# LB_BIT_w12_wirelessTransmitter_v03_2_2_O.net
KiCad netlist of a schematic drawn in EAGLE
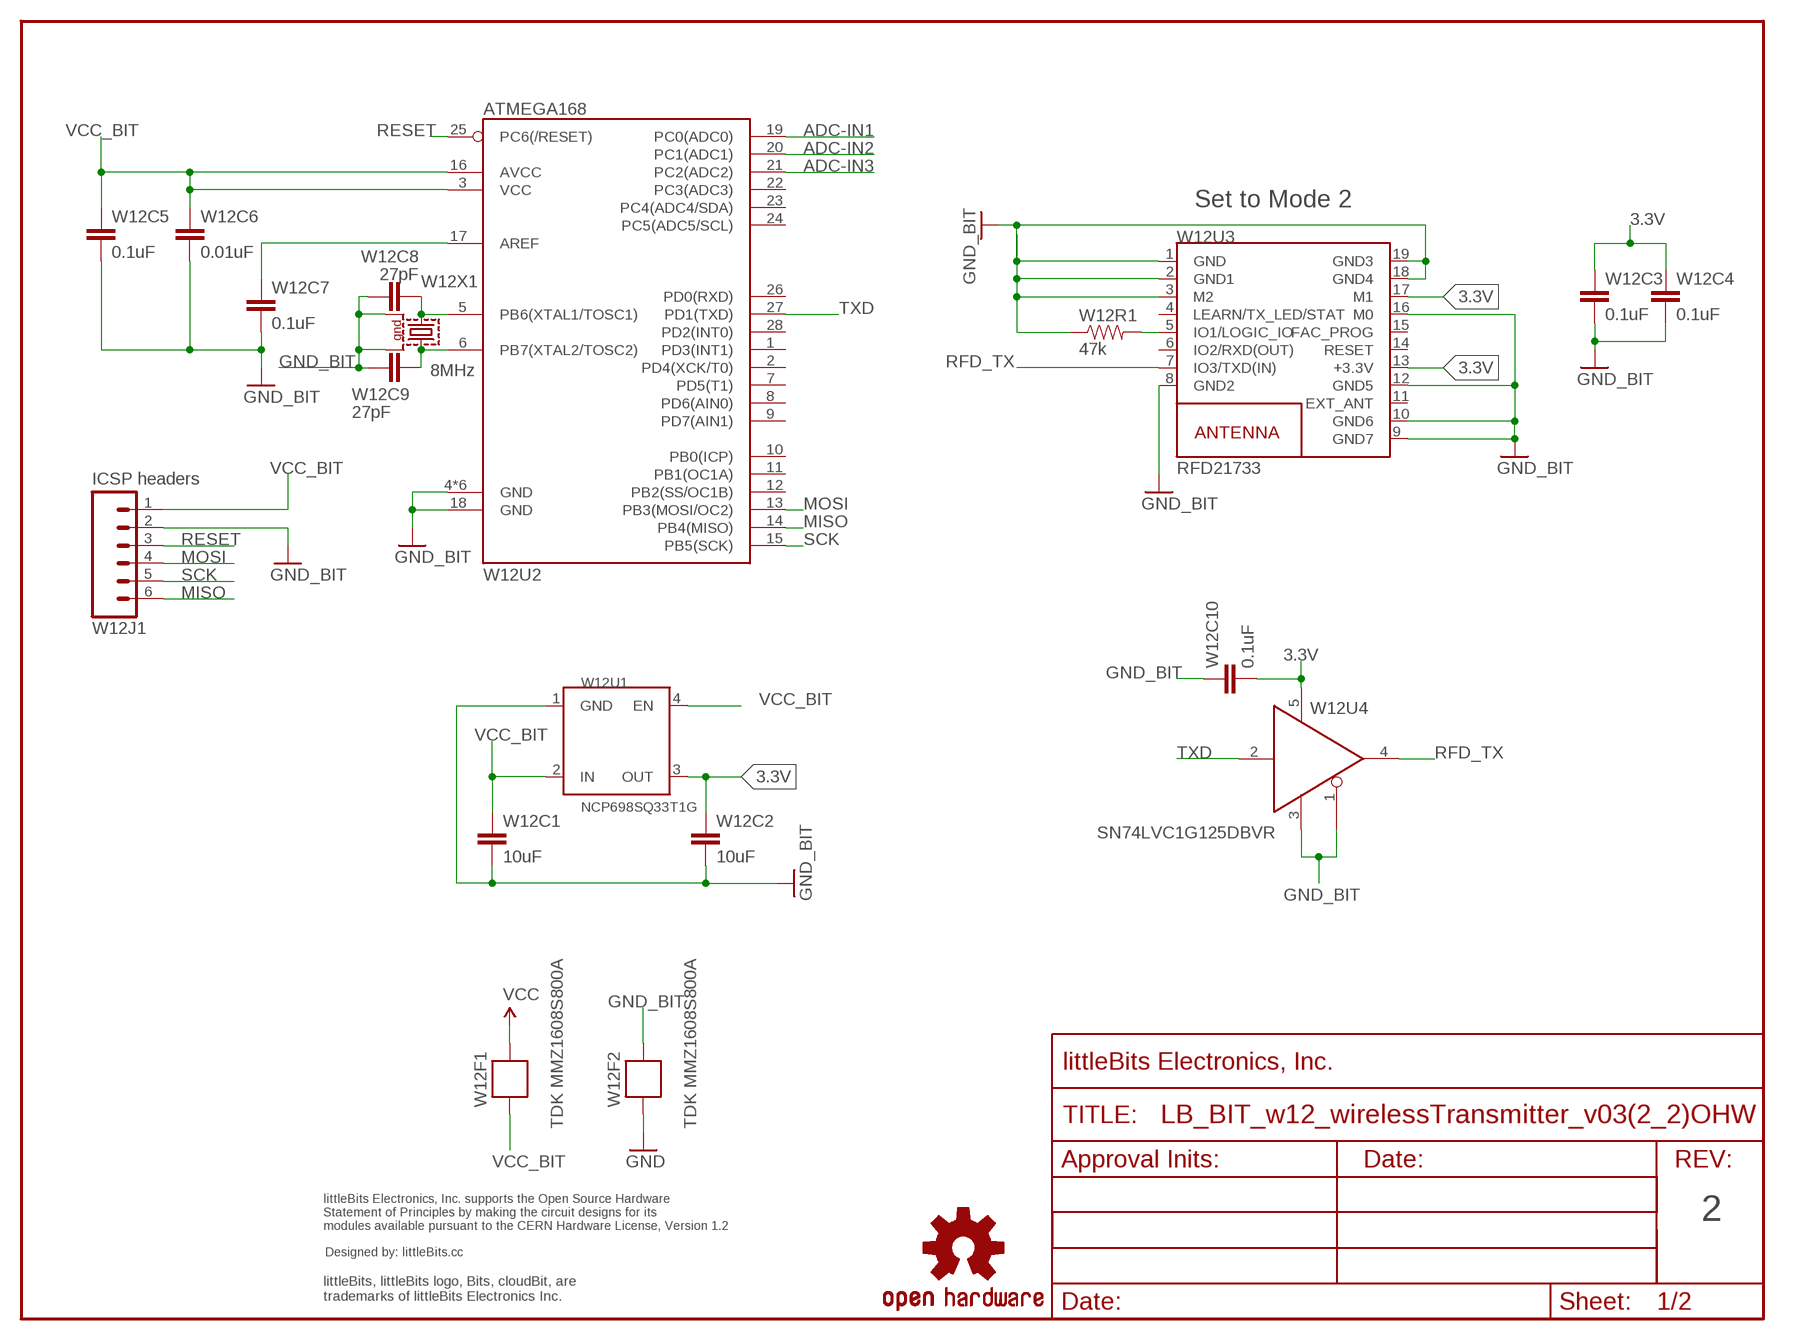
[diagram p0: schematic, sheet 1]
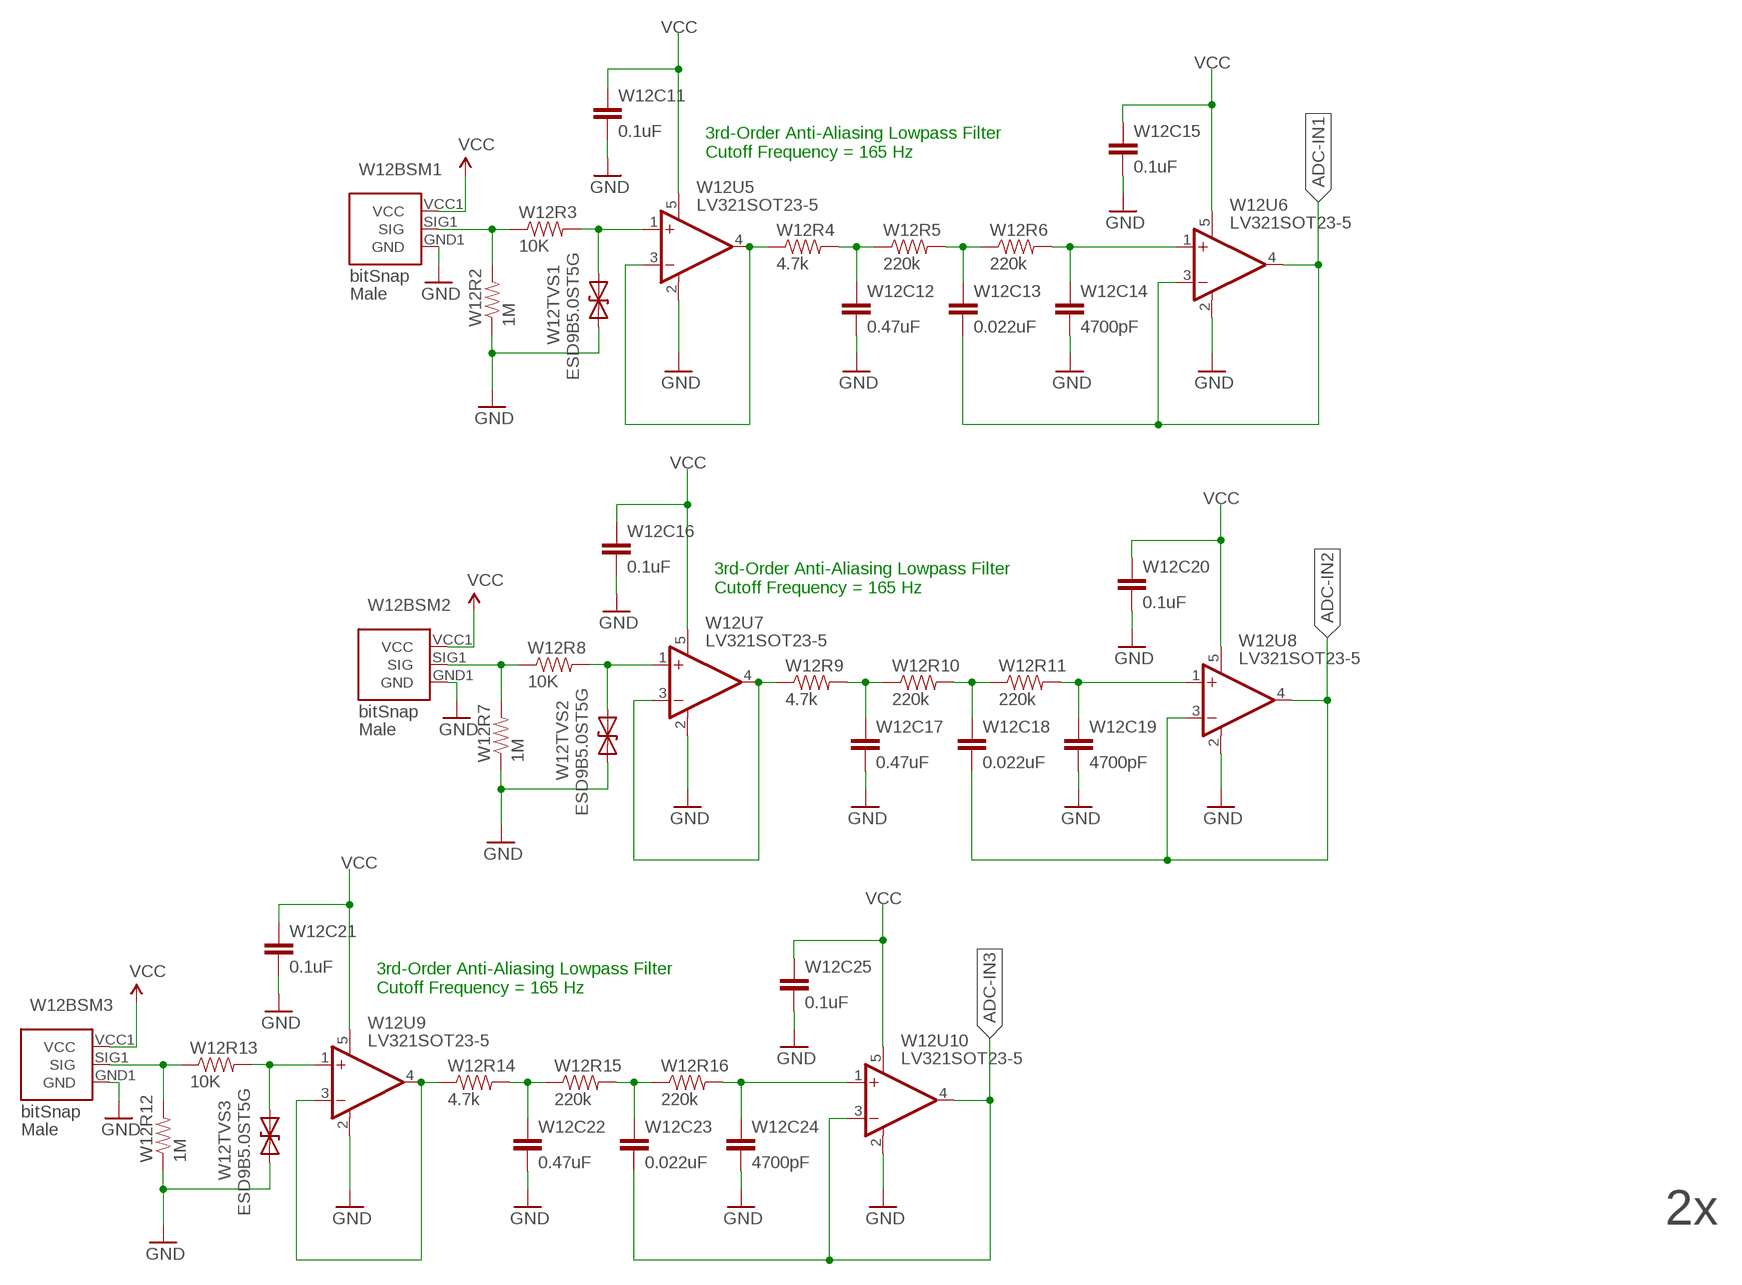
[diagram p1: schematic, sheet 2]

(export (version "E")
  (design (tool "Eeschema 10.0.6"))
  (components
    (comp (ref "W12BSM1")
      (value "BITSNAP_V03_MALE")
      (footprint "eagle-import:BITSNAP_V03_MALE")
      (libsource (lib "eagle-import") (part "BITSNAP_V03_MALE"))
    )
    (comp (ref "W12BSM2")
      (value "BITSNAP_V03_MALE")
      (footprint "eagle-import:BITSNAP_V03_MALE")
      (libsource (lib "eagle-import") (part "BITSNAP_V03_MALE"))
    )
    (comp (ref "W12BSM3")
      (value "BITSNAP_V03_MALE")
      (footprint "eagle-import:BITSNAP_V03_MALE")
      (libsource (lib "eagle-import") (part "BITSNAP_V03_MALE"))
    )
    (comp (ref "W12C11")
      (value "0.1uF")
      (footprint "eagle-import:0603-CAP")
      (libsource (lib "eagle-import") (part "CAP0603-CAP"))
    )
    (comp (ref "W12C12")
      (value "0.47uF")
      (footprint "eagle-import:CAP-0603")
      (libsource (lib "eagle-import") (part "CAPCAP-0603"))
    )
    (comp (ref "W12C13")
      (value "0.022uF")
      (footprint "eagle-import:CAP-0603")
      (libsource (lib "eagle-import") (part "CAPCAP-0603"))
    )
    (comp (ref "W12C14")
      (value "4700pF")
      (footprint "eagle-import:CAP-0603")
      (libsource (lib "eagle-import") (part "CAPCAP-0603"))
    )
    (comp (ref "W12C15")
      (value "0.1uF")
      (footprint "eagle-import:0603-CAP")
      (libsource (lib "eagle-import") (part "CAP0603-CAP"))
    )
    (comp (ref "W12C16")
      (value "0.1uF")
      (footprint "eagle-import:0603-CAP")
      (libsource (lib "eagle-import") (part "CAP0603-CAP"))
    )
    (comp (ref "W12C17")
      (value "0.47uF")
      (footprint "eagle-import:CAP-0603")
      (libsource (lib "eagle-import") (part "CAPCAP-0603"))
    )
    (comp (ref "W12C18")
      (value "0.022uF")
      (footprint "eagle-import:CAP-0603")
      (libsource (lib "eagle-import") (part "CAPCAP-0603"))
    )
    (comp (ref "W12C19")
      (value "4700pF")
      (footprint "eagle-import:CAP-0603")
      (libsource (lib "eagle-import") (part "CAPCAP-0603"))
    )
    (comp (ref "W12C20")
      (value "0.1uF")
      (footprint "eagle-import:0603-CAP")
      (libsource (lib "eagle-import") (part "CAP0603-CAP"))
    )
    (comp (ref "W12C21")
      (value "0.1uF")
      (footprint "eagle-import:0603-CAP")
      (libsource (lib "eagle-import") (part "CAP0603-CAP"))
    )
    (comp (ref "W12C22")
      (value "0.47uF")
      (footprint "eagle-import:CAP-0603")
      (libsource (lib "eagle-import") (part "CAPCAP-0603"))
    )
    (comp (ref "W12C23")
      (value "0.022uF")
      (footprint "eagle-import:CAP-0603")
      (libsource (lib "eagle-import") (part "CAPCAP-0603"))
    )
    (comp (ref "W12C24")
      (value "4700pF")
      (footprint "eagle-import:CAP-0603")
      (libsource (lib "eagle-import") (part "CAPCAP-0603"))
    )
    (comp (ref "W12C25")
      (value "0.1uF")
      (footprint "eagle-import:0603-CAP")
      (libsource (lib "eagle-import") (part "CAP0603-CAP"))
    )
    (comp (ref "W12R2")
      (value "1M")
      (footprint "eagle-import:0603-RES")
      (libsource (lib "eagle-import") (part "RESISTOR0603-RES"))
    )
    (comp (ref "W12R3")
      (value "10K")
      (footprint "eagle-import:0603-RES")
      (libsource (lib "eagle-import") (part "RESISTOR0603-RES"))
    )
    (comp (ref "W12R4")
      (value "4.7k")
      (footprint "eagle-import:RES-0603")
      (libsource (lib "eagle-import") (part "RESISTOR0603"))
    )
    (comp (ref "W12R5")
      (value "220k")
      (footprint "eagle-import:RES-0603")
      (libsource (lib "eagle-import") (part "RESISTOR0603"))
    )
    (comp (ref "W12R6")
      (value "220k")
      (footprint "eagle-import:RES-0603")
      (libsource (lib "eagle-import") (part "RESISTOR0603"))
    )
    (comp (ref "W12R7")
      (value "1M")
      (footprint "eagle-import:0603-RES")
      (libsource (lib "eagle-import") (part "RESISTOR0603-RES"))
    )
    (comp (ref "W12R8")
      (value "10K")
      (footprint "eagle-import:0603-RES")
      (libsource (lib "eagle-import") (part "RESISTOR0603-RES"))
    )
    (comp (ref "W12R9")
      (value "4.7k")
      (footprint "eagle-import:RES-0603")
      (libsource (lib "eagle-import") (part "RESISTOR0603"))
    )
    (comp (ref "W12R10")
      (value "220k")
      (footprint "eagle-import:RES-0603")
      (libsource (lib "eagle-import") (part "RESISTOR0603"))
    )
    (comp (ref "W12R11")
      (value "220k")
      (footprint "eagle-import:RES-0603")
      (libsource (lib "eagle-import") (part "RESISTOR0603"))
    )
    (comp (ref "W12R12")
      (value "1M")
      (footprint "eagle-import:0603-RES")
      (libsource (lib "eagle-import") (part "RESISTOR0603-RES"))
    )
    (comp (ref "W12R13")
      (value "10K")
      (footprint "eagle-import:0603-RES")
      (libsource (lib "eagle-import") (part "RESISTOR0603-RES"))
    )
    (comp (ref "W12R14")
      (value "4.7k")
      (footprint "eagle-import:RES-0603")
      (libsource (lib "eagle-import") (part "RESISTOR0603"))
    )
    (comp (ref "W12R15")
      (value "220k")
      (footprint "eagle-import:RES-0603")
      (libsource (lib "eagle-import") (part "RESISTOR0603"))
    )
    (comp (ref "W12R16")
      (value "220k")
      (footprint "eagle-import:RES-0603")
      (libsource (lib "eagle-import") (part "RESISTOR0603"))
    )
    (comp (ref "W12TVS1")
      (value "ESD9B5.0ST5G")
      (footprint "eagle-import:SOD-923")
      (libsource (lib "eagle-import") (part "DIODE-TVSSOD-923"))
    )
    (comp (ref "W12TVS2")
      (value "ESD9B5.0ST5G")
      (footprint "eagle-import:SOD-923")
      (libsource (lib "eagle-import") (part "DIODE-TVSSOD-923"))
    )
    (comp (ref "W12TVS3")
      (value "ESD9B5.0ST5G")
      (footprint "eagle-import:SOD-923")
      (libsource (lib "eagle-import") (part "DIODE-TVSSOD-923"))
    )
    (comp (ref "W12U5")
      (value "LV321SOT23-5")
      (footprint "eagle-import:SOT23-5")
      (libsource (lib "eagle-import") (part "LV321SOT23-5"))
    )
    (comp (ref "W12U6")
      (value "LV321SOT23-5")
      (footprint "eagle-import:SOT23-5")
      (libsource (lib "eagle-import") (part "LV321SOT23-5"))
    )
    (comp (ref "W12U7")
      (value "LV321SOT23-5")
      (footprint "eagle-import:SOT23-5")
      (libsource (lib "eagle-import") (part "LV321SOT23-5"))
    )
    (comp (ref "W12U8")
      (value "LV321SOT23-5")
      (footprint "eagle-import:SOT23-5")
      (libsource (lib "eagle-import") (part "LV321SOT23-5"))
    )
    (comp (ref "W12U9")
      (value "LV321SOT23-5")
      (footprint "eagle-import:SOT23-5")
      (libsource (lib "eagle-import") (part "LV321SOT23-5"))
    )
    (comp (ref "W12U10")
      (value "LV321SOT23-5")
      (footprint "eagle-import:SOT23-5")
      (libsource (lib "eagle-import") (part "LV321SOT23-5"))
    )
    (comp (ref "FRAME1")
      (value "FRAME-LETTER-OHWOHW")
      (footprint "eagle-import:FABDWG01-OHW")
      (libsource (lib "eagle-import") (part "FRAME-LETTER-OHWOHW"))
    )
    (comp (ref "U$15")
      (value "OSHWCREDIT")
      (footprint "eagle-import:OSHWCREDIT")
      (libsource (lib "eagle-import") (part "OSHWCREDIT"))
    )
    (comp (ref "U$31")
      (value "OSHW-LOGOL")
      (footprint "eagle-import:OSHW-LOGO-L")
      (libsource (lib "eagle-import") (part "OSHW-LOGOL"))
    )
    (comp (ref "W12C1")
      (value "10uF")
      (footprint "eagle-import:CAP-0603")
      (libsource (lib "eagle-import") (part "CAPCAP-0603"))
    )
    (comp (ref "W12C2")
      (value "10uF")
      (footprint "eagle-import:CAP-0603")
      (libsource (lib "eagle-import") (part "CAPCAP-0603"))
    )
    (comp (ref "W12C3")
      (value "0.1uF")
      (footprint "eagle-import:0603-CAP")
      (libsource (lib "eagle-import") (part "CAP0603-CAP"))
    )
    (comp (ref "W12C4")
      (value "0.1uF")
      (footprint "eagle-import:0603-CAP")
      (libsource (lib "eagle-import") (part "CAP0603-CAP"))
    )
    (comp (ref "W12C5")
      (value "0.1uF")
      (footprint "eagle-import:0603-CAP")
      (libsource (lib "eagle-import") (part "CAP0603-CAP"))
    )
    (comp (ref "W12C6")
      (value "0.01uF")
      (footprint "eagle-import:0603-CAP")
      (libsource (lib "eagle-import") (part "CAP0603-CAP"))
    )
    (comp (ref "W12C7")
      (value "0.1uF")
      (footprint "eagle-import:0603-CAP")
      (libsource (lib "eagle-import") (part "CAP0603-CAP"))
    )
    (comp (ref "W12C8")
      (value "27pF")
      (footprint "eagle-import:CAP-0603")
      (libsource (lib "eagle-import") (part "CAPCAP-0603"))
    )
    (comp (ref "W12C9")
      (value "27pF")
      (footprint "eagle-import:CAP-0603")
      (libsource (lib "eagle-import") (part "CAPCAP-0603"))
    )
    (comp (ref "W12C10")
      (value "0.1uF")
      (footprint "eagle-import:0603-CAP")
      (libsource (lib "eagle-import") (part "CAP0603-CAP"))
    )
    (comp (ref "W12F1")
      (value "TDK MMZ1608S800A")
      (footprint "eagle-import:R0603")
      (libsource (lib "eagle-import") (part "FERRITE-BEAD"))
    )
    (comp (ref "W12F2")
      (value "TDK MMZ1608S800A")
      (footprint "eagle-import:R0603")
      (libsource (lib "eagle-import") (part "FERRITE-BEAD"))
    )
    (comp (ref "W12J1")
      (value "ICSP headers")
      (footprint "eagle-import:SIP6-SM-0.1IN-NOS.S.")
      (libsource (lib "eagle-import") (part "HRD-60.1INCH_NO_SILKSCREEN"))
    )
    (comp (ref "W12R1")
      (value "47k")
      (footprint "eagle-import:0603-RES")
      (libsource (lib "eagle-import") (part "RESISTOR0603-RES"))
    )
    (comp (ref "W12U1")
      (value "NCP698SQ33T1G")
      (footprint "eagle-import:NCP698_SC82-AB")
      (libsource (lib "eagle-import") (part "NCP698"))
    )
    (comp (ref "W12U2")
      (value "ATMEGA168")
      (footprint "eagle-import:VQFN28")
      (libsource (lib "eagle-import") (part "ATMEGA168-28PINVFQFN-28"))
    )
    (comp (ref "W12U3")
      (value "RFD21733")
      (footprint "eagle-import:RFD21733")
      (libsource (lib "eagle-import") (part "RFD_CHIP"))
    )
    (comp (ref "W12U4")
      (value "SN74LVC1G125DBVR")
      (footprint "eagle-import:SOT23-5")
      (libsource (lib "eagle-import") (part "5V_TO_3.3V_LEVEL-SHIFTERSOT23-5"))
    )
    (comp (ref "W12X1")
      (value "8MHz")
      (footprint "eagle-import:CRYSTAL-SMD-7B-SERIES-5X3.2MM")
      (fields (field (name "MFG") "TXC") (field (name "MPN") "7B SERIES"))
      (libsource (lib "eagle-import") (part "CRYSTAL-SMD-7B-SERIES-TXC"))
    )
  )
  (nets
    (net (code "1") (name "3.3V") (class "Default")
      (node (ref "W12C10") (pin "2") (pinfunction "2_2") (pintype "passive"))
      (node (ref "W12C2") (pin "1") (pinfunction "1_1") (pintype "passive"))
      (node (ref "W12C3") (pin "1") (pinfunction "1_1") (pintype "passive"))
      (node (ref "W12C4") (pin "1") (pinfunction "1_1") (pintype "passive"))
      (node (ref "W12U1") (pin "3") (pinfunction "OUT_3") (pintype "bidirectional"))
      (node (ref "W12U3") (pin "13") (pinfunction "+3.3V_13") (pintype "bidirectional"))
      (node (ref "W12U3") (pin "17") (pinfunction "M1_17") (pintype "bidirectional"))
      (node (ref "W12U4") (pin "5") (pinfunction "5_5") (pintype "bidirectional"))
    )
    (net (code "2") (name "ADC-IN1") (class "Default")
      (node (ref "W12C13") (pin "2") (pinfunction "2_2") (pintype "passive"))
      (node (ref "W12U2") (pin "19") (pinfunction "PC0(ADC0)_19") (pintype "bidirectional"))
      (node (ref "W12U6") (pin "3") (pinfunction "-IN_3") (pintype "input"))
      (node (ref "W12U6") (pin "4") (pinfunction "OUT_4") (pintype "output"))
    )
    (net (code "3") (name "ADC-IN2") (class "Default")
      (node (ref "W12C18") (pin "2") (pinfunction "2_2") (pintype "passive"))
      (node (ref "W12U2") (pin "20") (pinfunction "PC1(ADC1)_20") (pintype "bidirectional"))
      (node (ref "W12U8") (pin "3") (pinfunction "-IN_3") (pintype "input"))
      (node (ref "W12U8") (pin "4") (pinfunction "OUT_4") (pintype "output"))
    )
    (net (code "4") (name "ADC-IN3") (class "Default")
      (node (ref "W12C23") (pin "2") (pinfunction "2_2") (pintype "passive"))
      (node (ref "W12U10") (pin "3") (pinfunction "-IN_3") (pintype "input"))
      (node (ref "W12U10") (pin "4") (pinfunction "OUT_4") (pintype "output"))
      (node (ref "W12U2") (pin "21") (pinfunction "PC2(ADC2)_21") (pintype "bidirectional"))
    )
    (net (code "5") (name "GND") (class "Default")
      (node (ref "W12BSM1") (pin "GND1") (pinfunction "GND_GND1") (pintype "bidirectional"))
      (node (ref "W12BSM2") (pin "GND1") (pinfunction "GND_GND1") (pintype "bidirectional"))
      (node (ref "W12BSM3") (pin "GND1") (pinfunction "GND_GND1") (pintype "bidirectional"))
      (node (ref "W12C11") (pin "2") (pinfunction "2_2") (pintype "passive"))
      (node (ref "W12C12") (pin "2") (pinfunction "2_2") (pintype "passive"))
      (node (ref "W12C14") (pin "2") (pinfunction "2_2") (pintype "passive"))
      (node (ref "W12C15") (pin "2") (pinfunction "2_2") (pintype "passive"))
      (node (ref "W12C16") (pin "2") (pinfunction "2_2") (pintype "passive"))
      (node (ref "W12C17") (pin "2") (pinfunction "2_2") (pintype "passive"))
      (node (ref "W12C19") (pin "2") (pinfunction "2_2") (pintype "passive"))
      (node (ref "W12C20") (pin "2") (pinfunction "2_2") (pintype "passive"))
      (node (ref "W12C21") (pin "2") (pinfunction "2_2") (pintype "passive"))
      (node (ref "W12C22") (pin "2") (pinfunction "2_2") (pintype "passive"))
      (node (ref "W12C24") (pin "2") (pinfunction "2_2") (pintype "passive"))
      (node (ref "W12C25") (pin "2") (pinfunction "2_2") (pintype "passive"))
      (node (ref "W12F2") (pin "2") (pinfunction "P$2_2") (pintype "bidirectional"))
      (node (ref "W12R12") (pin "1") (pinfunction "1_1") (pintype "passive"))
      (node (ref "W12R2") (pin "1") (pinfunction "1_1") (pintype "passive"))
      (node (ref "W12R7") (pin "1") (pinfunction "1_1") (pintype "passive"))
      (node (ref "W12TVS1") (pin "1") (pinfunction "A_1") (pintype "passive"))
      (node (ref "W12TVS2") (pin "1") (pinfunction "A_1") (pintype "passive"))
      (node (ref "W12TVS3") (pin "1") (pinfunction "A_1") (pintype "passive"))
      (node (ref "W12U10") (pin "2") (pinfunction "V-_2") (pintype "power_in"))
      (node (ref "W12U5") (pin "2") (pinfunction "V-_2") (pintype "power_in"))
      (node (ref "W12U6") (pin "2") (pinfunction "V-_2") (pintype "power_in"))
      (node (ref "W12U7") (pin "2") (pinfunction "V-_2") (pintype "power_in"))
      (node (ref "W12U8") (pin "2") (pinfunction "V-_2") (pintype "power_in"))
      (node (ref "W12U9") (pin "2") (pinfunction "V-_2") (pintype "power_in"))
    )
    (net (code "6") (name "GND_BIT") (class "Default")
      (node (ref "W12C1") (pin "2") (pinfunction "2_2") (pintype "passive"))
      (node (ref "W12C10") (pin "1") (pinfunction "1_1") (pintype "passive"))
      (node (ref "W12C2") (pin "2") (pinfunction "2_2") (pintype "passive"))
      (node (ref "W12C3") (pin "2") (pinfunction "2_2") (pintype "passive"))
      (node (ref "W12C4") (pin "2") (pinfunction "2_2") (pintype "passive"))
      (node (ref "W12C5") (pin "2") (pinfunction "2_2") (pintype "passive"))
      (node (ref "W12C6") (pin "2") (pinfunction "2_2") (pintype "passive"))
      (node (ref "W12C7") (pin "2") (pinfunction "2_2") (pintype "passive"))
      (node (ref "W12C8") (pin "1") (pinfunction "1_1") (pintype "passive"))
      (node (ref "W12C9") (pin "2") (pinfunction "2_2") (pintype "passive"))
      (node (ref "W12F2") (pin "1") (pinfunction "P$1_1") (pintype "bidirectional"))
      (node (ref "W12J1") (pin "2") (pinfunction "2_2") (pintype "passive"))
      (node (ref "W12R1") (pin "1") (pinfunction "1_1") (pintype "passive"))
      (node (ref "W12U1") (pin "1") (pinfunction "GND_1") (pintype "bidirectional"))
      (node (ref "W12U2") (pin "18") (pinfunction "GND_18") (pintype "bidirectional"))
      (node (ref "W12U2") (pin "4") (pinfunction "GND_4") (pintype "bidirectional"))
      (node (ref "W12U2") (pin "TH") (pinfunction "GND_TH") (pintype "bidirectional"))
      (node (ref "W12U2") (pin "TH@1") (pinfunction "GND_TH@1") (pintype "bidirectional"))
      (node (ref "W12U2") (pin "TH@2") (pinfunction "GND_TH@2") (pintype "bidirectional"))
      (node (ref "W12U2") (pin "TH@3") (pinfunction "GND_TH@3") (pintype "bidirectional"))
      (node (ref "W12U2") (pin "TH@4") (pinfunction "GND_TH@4") (pintype "bidirectional"))
      (node (ref "W12U3") (pin "1") (pinfunction "GND_1") (pintype "bidirectional"))
      (node (ref "W12U3") (pin "10") (pinfunction "GND6_10") (pintype "bidirectional"))
      (node (ref "W12U3") (pin "12") (pinfunction "GND5_12") (pintype "bidirectional"))
      (node (ref "W12U3") (pin "16") (pinfunction "M0_16") (pintype "bidirectional"))
      (node (ref "W12U3") (pin "18") (pinfunction "GND4_18") (pintype "bidirectional"))
      (node (ref "W12U3") (pin "19") (pinfunction "GND3_19") (pintype "bidirectional"))
      (node (ref "W12U3") (pin "2") (pinfunction "GND1_2") (pintype "bidirectional"))
      (node (ref "W12U3") (pin "3") (pinfunction "M2_3") (pintype "bidirectional"))
      (node (ref "W12U3") (pin "8") (pinfunction "GND2_8") (pintype "bidirectional"))
      (node (ref "W12U3") (pin "9") (pinfunction "GND7_9") (pintype "bidirectional"))
      (node (ref "W12U4") (pin "1") (pinfunction "1_1") (pintype "bidirectional"))
      (node (ref "W12U4") (pin "3") (pinfunction "3_3") (pintype "bidirectional"))
      (node (ref "W12X1") (pin "P$2") (pinfunction "2_P$2") (pintype "passive"))
      (node (ref "W12X1") (pin "P$4") (pinfunction "4_P$4") (pintype "passive"))
    )
    (net (code "7") (name "MISO") (class "Default")
      (node (ref "W12J1") (pin "6") (pinfunction "6_6") (pintype "passive"))
      (node (ref "W12U2") (pin "14") (pinfunction "PB4(MISO)_14") (pintype "bidirectional"))
    )
    (net (code "8") (name "MOSI") (class "Default")
      (node (ref "W12J1") (pin "4") (pinfunction "4_4") (pintype "passive"))
      (node (ref "W12U2") (pin "13") (pinfunction "PB3(MOSI/OC2)_13") (pintype "bidirectional"))
    )
    (net (code "9") (name "Net-(W12BSM1-SIG)") (class "Default")
      (node (ref "W12BSM1") (pin "SIG1") (pinfunction "SIG_SIG1") (pintype "bidirectional"))
      (node (ref "W12R2") (pin "2") (pinfunction "2_2") (pintype "passive"))
      (node (ref "W12R3") (pin "1") (pinfunction "1_1") (pintype "passive"))
    )
    (net (code "10") (name "Net-(W12BSM2-SIG)") (class "Default")
      (node (ref "W12BSM2") (pin "SIG1") (pinfunction "SIG_SIG1") (pintype "bidirectional"))
      (node (ref "W12R7") (pin "2") (pinfunction "2_2") (pintype "passive"))
      (node (ref "W12R8") (pin "1") (pinfunction "1_1") (pintype "passive"))
    )
    (net (code "11") (name "Net-(W12BSM3-SIG)") (class "Default")
      (node (ref "W12BSM3") (pin "SIG1") (pinfunction "SIG_SIG1") (pintype "bidirectional"))
      (node (ref "W12R12") (pin "2") (pinfunction "2_2") (pintype "passive"))
      (node (ref "W12R13") (pin "1") (pinfunction "1_1") (pintype "passive"))
    )
    (net (code "12") (name "Net-(W12C12-Pad1)") (class "Default")
      (node (ref "W12C12") (pin "1") (pinfunction "1_1") (pintype "passive"))
      (node (ref "W12R4") (pin "2") (pinfunction "2_2") (pintype "passive"))
      (node (ref "W12R5") (pin "1") (pinfunction "1_1") (pintype "passive"))
    )
    (net (code "13") (name "Net-(W12C13-Pad1)") (class "Default")
      (node (ref "W12C13") (pin "1") (pinfunction "1_1") (pintype "passive"))
      (node (ref "W12R5") (pin "2") (pinfunction "2_2") (pintype "passive"))
      (node (ref "W12R6") (pin "1") (pinfunction "1_1") (pintype "passive"))
    )
    (net (code "14") (name "Net-(W12C17-Pad1)") (class "Default")
      (node (ref "W12C17") (pin "1") (pinfunction "1_1") (pintype "passive"))
      (node (ref "W12R10") (pin "1") (pinfunction "1_1") (pintype "passive"))
      (node (ref "W12R9") (pin "2") (pinfunction "2_2") (pintype "passive"))
    )
    (net (code "15") (name "Net-(W12C18-Pad1)") (class "Default")
      (node (ref "W12C18") (pin "1") (pinfunction "1_1") (pintype "passive"))
      (node (ref "W12R10") (pin "2") (pinfunction "2_2") (pintype "passive"))
      (node (ref "W12R11") (pin "1") (pinfunction "1_1") (pintype "passive"))
    )
    (net (code "16") (name "Net-(W12C22-Pad1)") (class "Default")
      (node (ref "W12C22") (pin "1") (pinfunction "1_1") (pintype "passive"))
      (node (ref "W12R14") (pin "2") (pinfunction "2_2") (pintype "passive"))
      (node (ref "W12R15") (pin "1") (pinfunction "1_1") (pintype "passive"))
    )
    (net (code "17") (name "Net-(W12C23-Pad1)") (class "Default")
      (node (ref "W12C23") (pin "1") (pinfunction "1_1") (pintype "passive"))
      (node (ref "W12R15") (pin "2") (pinfunction "2_2") (pintype "passive"))
      (node (ref "W12R16") (pin "1") (pinfunction "1_1") (pintype "passive"))
    )
    (net (code "18") (name "Net-(W12TVS1-C)") (class "Default")
      (node (ref "W12R3") (pin "2") (pinfunction "2_2") (pintype "passive"))
      (node (ref "W12TVS1") (pin "2") (pinfunction "C_2") (pintype "passive"))
      (node (ref "W12U5") (pin "1") (pinfunction "+IN_1") (pintype "input"))
    )
    (net (code "19") (name "Net-(W12TVS2-C)") (class "Default")
      (node (ref "W12R8") (pin "2") (pinfunction "2_2") (pintype "passive"))
      (node (ref "W12TVS2") (pin "2") (pinfunction "C_2") (pintype "passive"))
      (node (ref "W12U7") (pin "1") (pinfunction "+IN_1") (pintype "input"))
    )
    (net (code "20") (name "Net-(W12TVS3-C)") (class "Default")
      (node (ref "W12R13") (pin "2") (pinfunction "2_2") (pintype "passive"))
      (node (ref "W12TVS3") (pin "2") (pinfunction "C_2") (pintype "passive"))
      (node (ref "W12U9") (pin "1") (pinfunction "+IN_1") (pintype "input"))
    )
    (net (code "21") (name "Net-(W12U2-AREF)") (class "Default")
      (node (ref "W12C7") (pin "1") (pinfunction "1_1") (pintype "passive"))
      (node (ref "W12U2") (pin "17") (pinfunction "AREF_17") (pintype "bidirectional"))
    )
    (net (code "22") (name "Net-(W12U2-PB6(XTAL1{slash}TOSC1))") (class "Default")
      (node (ref "W12C8") (pin "2") (pinfunction "2_2") (pintype "passive"))
      (node (ref "W12U2") (pin "5") (pinfunction "PB6(XTAL1/TOSC1)_5") (pintype "bidirectional"))
      (node (ref "W12X1") (pin "P$1") (pinfunction "1_P$1") (pintype "passive"))
    )
    (net (code "23") (name "Net-(W12U2-PB7(XTAL2{slash}TOSC2))") (class "Default")
      (node (ref "W12C9") (pin "1") (pinfunction "1_1") (pintype "passive"))
      (node (ref "W12U2") (pin "6") (pinfunction "PB7(XTAL2/TOSC2)_6") (pintype "bidirectional"))
      (node (ref "W12X1") (pin "P$3") (pinfunction "3_P$3") (pintype "passive"))
    )
    (net (code "24") (name "Net-(W12U3-IO1{slash}LOGIC_IO)") (class "Default")
      (node (ref "W12R1") (pin "2") (pinfunction "2_2") (pintype "passive"))
      (node (ref "W12U3") (pin "5") (pinfunction "IO1/LOGIC_IO_5") (pintype "bidirectional"))
    )
    (net (code "25") (name "Net-(W12U5--IN)") (class "Default")
      (node (ref "W12R4") (pin "1") (pinfunction "1_1") (pintype "passive"))
      (node (ref "W12U5") (pin "3") (pinfunction "-IN_3") (pintype "input"))
      (node (ref "W12U5") (pin "4") (pinfunction "OUT_4") (pintype "output"))
    )
    (net (code "26") (name "Net-(W12U6-+IN)") (class "Default")
      (node (ref "W12C14") (pin "1") (pinfunction "1_1") (pintype "passive"))
      (node (ref "W12R6") (pin "2") (pinfunction "2_2") (pintype "passive"))
      (node (ref "W12U6") (pin "1") (pinfunction "+IN_1") (pintype "input"))
    )
    (net (code "27") (name "Net-(W12U7--IN)") (class "Default")
      (node (ref "W12R9") (pin "1") (pinfunction "1_1") (pintype "passive"))
      (node (ref "W12U7") (pin "3") (pinfunction "-IN_3") (pintype "input"))
      (node (ref "W12U7") (pin "4") (pinfunction "OUT_4") (pintype "output"))
    )
    (net (code "28") (name "Net-(W12U8-+IN)") (class "Default")
      (node (ref "W12C19") (pin "1") (pinfunction "1_1") (pintype "passive"))
      (node (ref "W12R11") (pin "2") (pinfunction "2_2") (pintype "passive"))
      (node (ref "W12U8") (pin "1") (pinfunction "+IN_1") (pintype "input"))
    )
    (net (code "29") (name "Net-(W12U9--IN)") (class "Default")
      (node (ref "W12R14") (pin "1") (pinfunction "1_1") (pintype "passive"))
      (node (ref "W12U9") (pin "3") (pinfunction "-IN_3") (pintype "input"))
      (node (ref "W12U9") (pin "4") (pinfunction "OUT_4") (pintype "output"))
    )
    (net (code "30") (name "Net-(W12U10-+IN)") (class "Default")
      (node (ref "W12C24") (pin "1") (pinfunction "1_1") (pintype "passive"))
      (node (ref "W12R16") (pin "2") (pinfunction "2_2") (pintype "passive"))
      (node (ref "W12U10") (pin "1") (pinfunction "+IN_1") (pintype "input"))
    )
    (net (code "31") (name "RESET") (class "Default")
      (node (ref "W12J1") (pin "3") (pinfunction "3_3") (pintype "passive"))
      (node (ref "W12U2") (pin "25") (pinfunction "PC6(/RESET)_25") (pintype "bidirectional"))
    )
    (net (code "32") (name "RFD_TX") (class "Default")
      (node (ref "W12U3") (pin "7") (pinfunction "IO3/TXD(IN)_7") (pintype "bidirectional"))
      (node (ref "W12U4") (pin "4") (pinfunction "4_4") (pintype "bidirectional"))
    )
    (net (code "33") (name "SCK") (class "Default")
      (node (ref "W12J1") (pin "5") (pinfunction "5_5") (pintype "passive"))
      (node (ref "W12U2") (pin "15") (pinfunction "PB5(SCK)_15") (pintype "bidirectional"))
    )
    (net (code "34") (name "TXD") (class "Default")
      (node (ref "W12U2") (pin "27") (pinfunction "PD1(TXD)_27") (pintype "bidirectional"))
      (node (ref "W12U4") (pin "2") (pinfunction "2_2") (pintype "bidirectional"))
    )
    (net (code "35") (name "VCC") (class "Default")
      (node (ref "W12BSM1") (pin "VCC1") (pinfunction "VCC_VCC1") (pintype "bidirectional"))
      (node (ref "W12BSM2") (pin "VCC1") (pinfunction "VCC_VCC1") (pintype "bidirectional"))
      (node (ref "W12BSM3") (pin "VCC1") (pinfunction "VCC_VCC1") (pintype "bidirectional"))
      (node (ref "W12C11") (pin "1") (pinfunction "1_1") (pintype "passive"))
      (node (ref "W12C15") (pin "1") (pinfunction "1_1") (pintype "passive"))
      (node (ref "W12C16") (pin "1") (pinfunction "1_1") (pintype "passive"))
      (node (ref "W12C20") (pin "1") (pinfunction "1_1") (pintype "passive"))
      (node (ref "W12C21") (pin "1") (pinfunction "1_1") (pintype "passive"))
      (node (ref "W12C25") (pin "1") (pinfunction "1_1") (pintype "passive"))
      (node (ref "W12F1") (pin "1") (pinfunction "P$1_1") (pintype "bidirectional"))
      (node (ref "W12U10") (pin "5") (pinfunction "V+_5") (pintype "power_in"))
      (node (ref "W12U5") (pin "5") (pinfunction "V+_5") (pintype "power_in"))
      (node (ref "W12U6") (pin "5") (pinfunction "V+_5") (pintype "power_in"))
      (node (ref "W12U7") (pin "5") (pinfunction "V+_5") (pintype "power_in"))
      (node (ref "W12U8") (pin "5") (pinfunction "V+_5") (pintype "power_in"))
      (node (ref "W12U9") (pin "5") (pinfunction "V+_5") (pintype "power_in"))
    )
    (net (code "36") (name "VCC_BIT") (class "Default")
      (node (ref "W12C1") (pin "1") (pinfunction "1_1") (pintype "passive"))
      (node (ref "W12C5") (pin "1") (pinfunction "1_1") (pintype "passive"))
      (node (ref "W12C6") (pin "1") (pinfunction "1_1") (pintype "passive"))
      (node (ref "W12F1") (pin "2") (pinfunction "P$2_2") (pintype "bidirectional"))
      (node (ref "W12J1") (pin "1") (pinfunction "1_1") (pintype "passive"))
      (node (ref "W12U1") (pin "2") (pinfunction "IN_2") (pintype "bidirectional"))
      (node (ref "W12U1") (pin "4") (pinfunction "EN_4") (pintype "bidirectional"))
      (node (ref "W12U2") (pin "16") (pinfunction "AVCC_16") (pintype "bidirectional"))
      (node (ref "W12U2") (pin "3") (pinfunction "VCC_3") (pintype "bidirectional"))
    )
    (net (code "37") (name "unconnected-(W12U2-PB0(ICP)-Pad10)") (class "Default")
      (node (ref "W12U2") (pin "10") (pinfunction "PB0(ICP)_10") (pintype "bidirectional"))
    )
    (net (code "38") (name "unconnected-(W12U2-PB1(OC1A)-Pad11)") (class "Default")
      (node (ref "W12U2") (pin "11") (pinfunction "PB1(OC1A)_11") (pintype "bidirectional"))
    )
    (net (code "39") (name "unconnected-(W12U2-PB2(SS{slash}OC1B)-Pad12)") (class "Default")
      (node (ref "W12U2") (pin "12") (pinfunction "PB2(SS/OC1B)_12") (pintype "bidirectional"))
    )
    (net (code "40") (name "unconnected-(W12U2-PC3(ADC3)-Pad22)") (class "Default")
      (node (ref "W12U2") (pin "22") (pinfunction "PC3(ADC3)_22") (pintype "bidirectional"))
    )
    (net (code "41") (name "unconnected-(W12U2-PC4(ADC4{slash}SDA)-Pad23)") (class "Default")
      (node (ref "W12U2") (pin "23") (pinfunction "PC4(ADC4/SDA)_23") (pintype "bidirectional"))
    )
    (net (code "42") (name "unconnected-(W12U2-PC5(ADC5{slash}SCL)-Pad24)") (class "Default")
      (node (ref "W12U2") (pin "24") (pinfunction "PC5(ADC5/SCL)_24") (pintype "bidirectional"))
    )
    (net (code "43") (name "unconnected-(W12U2-PD0(RXD)-Pad26)") (class "Default")
      (node (ref "W12U2") (pin "26") (pinfunction "PD0(RXD)_26") (pintype "bidirectional"))
    )
    (net (code "44") (name "unconnected-(W12U2-PD2(INT0)-Pad28)") (class "Default")
      (node (ref "W12U2") (pin "28") (pinfunction "PD2(INT0)_28") (pintype "bidirectional"))
    )
    (net (code "45") (name "unconnected-(W12U2-PD3(INT1)-Pad1)") (class "Default")
      (node (ref "W12U2") (pin "1") (pinfunction "PD3(INT1)_1") (pintype "bidirectional"))
    )
    (net (code "46") (name "unconnected-(W12U2-PD4(XCK{slash}T0)-Pad2)") (class "Default")
      (node (ref "W12U2") (pin "2") (pinfunction "PD4(XCK/T0)_2") (pintype "bidirectional"))
    )
    (net (code "47") (name "unconnected-(W12U2-PD5(T1)-Pad7)") (class "Default")
      (node (ref "W12U2") (pin "7") (pinfunction "PD5(T1)_7") (pintype "bidirectional"))
    )
    (net (code "48") (name "unconnected-(W12U2-PD6(AIN0)-Pad8)") (class "Default")
      (node (ref "W12U2") (pin "8") (pinfunction "PD6(AIN0)_8") (pintype "bidirectional"))
    )
    (net (code "49") (name "unconnected-(W12U2-PD7(AIN1)-Pad9)") (class "Default")
      (node (ref "W12U2") (pin "9") (pinfunction "PD7(AIN1)_9") (pintype "bidirectional"))
    )
    (net (code "50") (name "unconnected-(W12U3-EXT_ANT-Pad11)") (class "Default")
      (node (ref "W12U3") (pin "11") (pinfunction "EXT_ANT_11") (pintype "bidirectional"))
    )
    (net (code "51") (name "unconnected-(W12U3-FAC_PROG-Pad15)") (class "Default")
      (node (ref "W12U3") (pin "15") (pinfunction "FAC_PROG_15") (pintype "bidirectional"))
    )
    (net (code "52") (name "unconnected-(W12U3-IO2{slash}RXD(OUT)-Pad6)") (class "Default")
      (node (ref "W12U3") (pin "6") (pinfunction "IO2/RXD(OUT)_6") (pintype "bidirectional"))
    )
    (net (code "53") (name "unconnected-(W12U3-LEARN{slash}TX_LED{slash}STAT-Pad4)") (class "Default")
      (node (ref "W12U3") (pin "4") (pinfunction "LEARN/TX_LED/STAT_4") (pintype "bidirectional"))
    )
    (net (code "54") (name "unconnected-(W12U3-RESET-Pad14)") (class "Default")
      (node (ref "W12U3") (pin "14") (pinfunction "RESET_14") (pintype "bidirectional"))
    )
  )
)
